# Sheet1.net
KiCad netlist of a schematic drawn in Altium Designer
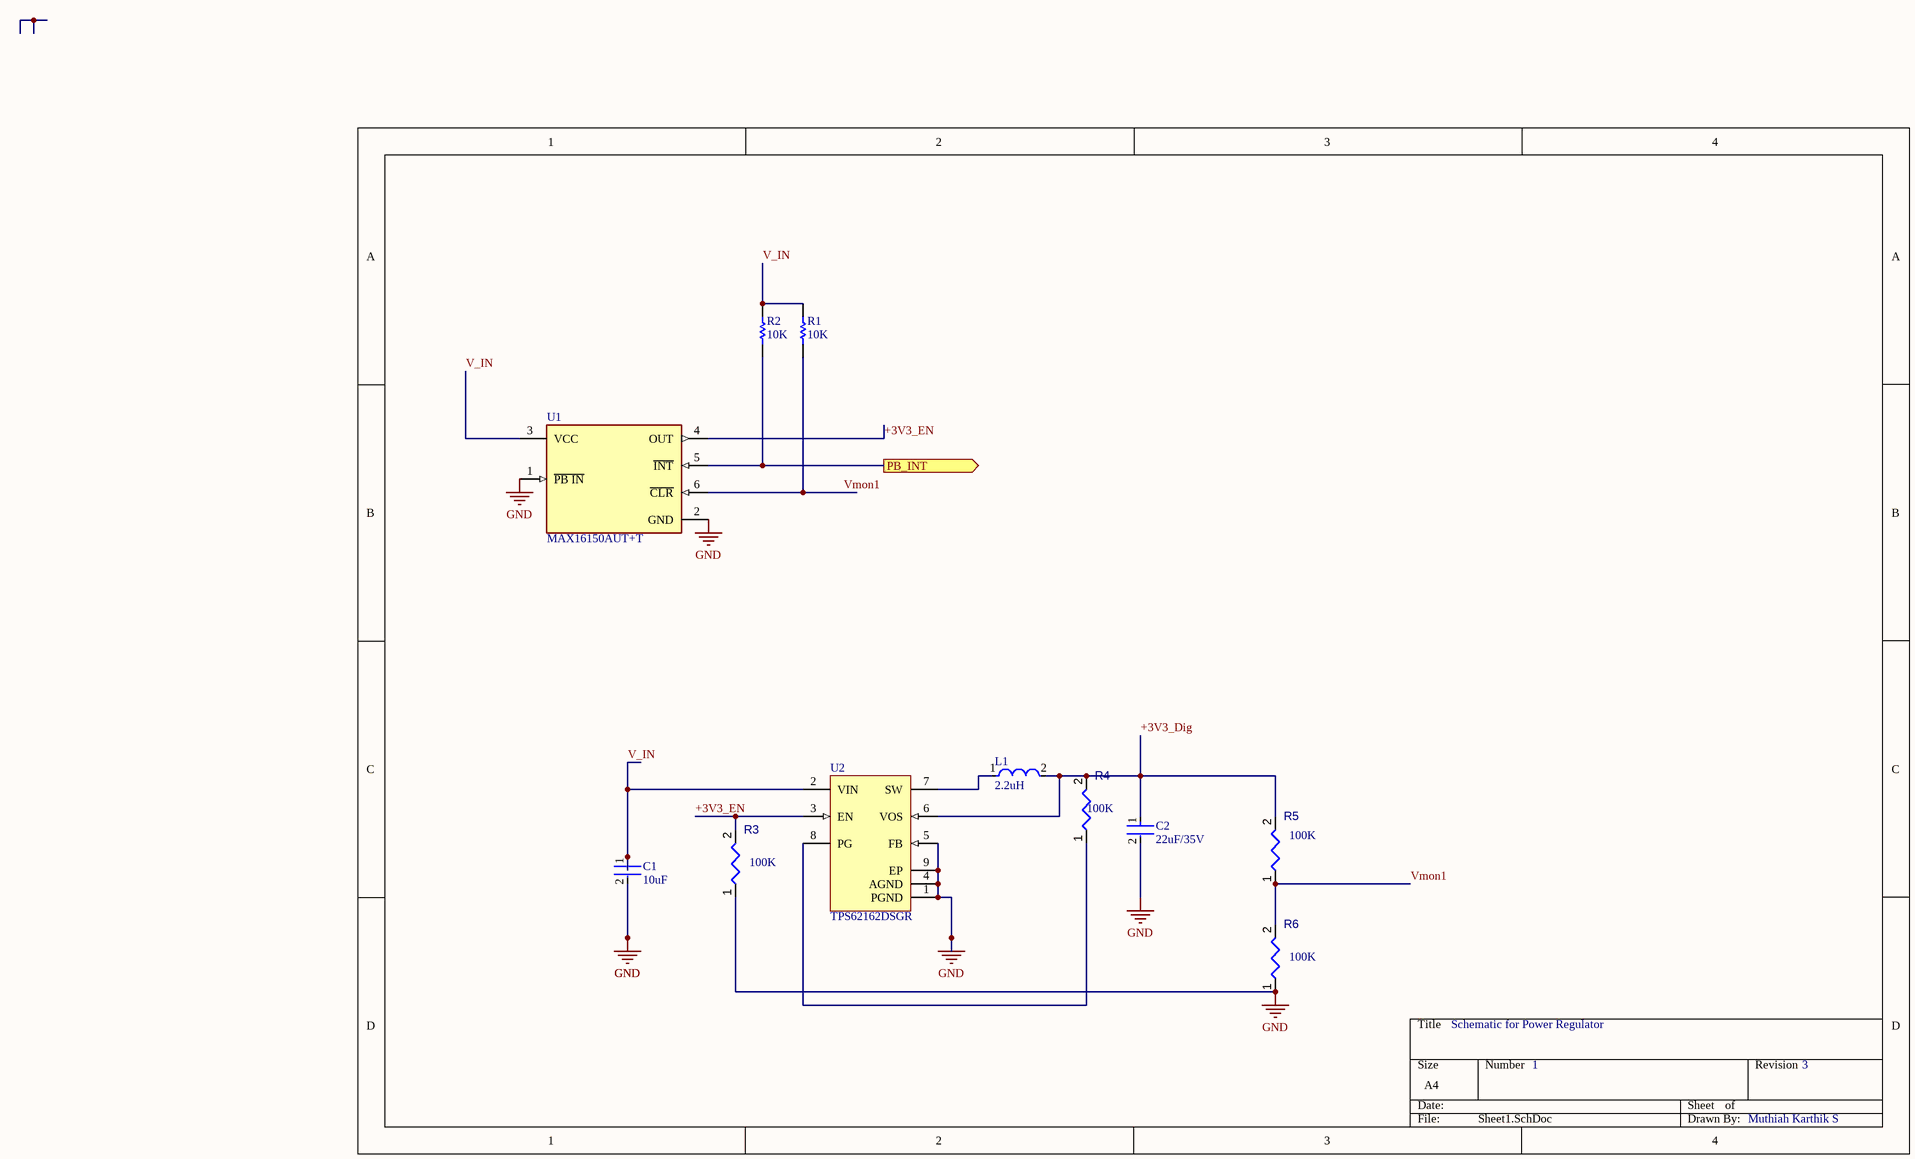
[diagram p0: Sheet1.SchDoc]

(export (version "E")
  (design (tool "Eeschema 10.0.6"))
  (components
    (comp (ref "C1")
      (value "10uF")
      (footprint "FP-CL21-IPC_C")
      (description "CL21 Series 0805 150nF 25V ±10% Tolerance X7R Multilayer Ceramic Chip Capacitor")
      (fields (field (name "TOLERANCE") "10%"))
      (libsource (lib "Altium Content Vault") (part "b4654b650e69147ec39a6b967a45e02"))
    )
    (comp (ref "C2")
      (value "22uF/35V")
      (footprint "FP-CL21-IPC_C")
      (description "CL21 Series 0805 150nF 25V ±10% Tolerance X7R Multilayer Ceramic Chip Capacitor")
      (fields (field (name "TOLERANCE") "10%"))
      (libsource (lib "Altium Content Vault") (part "b4654b650e69147ec39a6b967a45e02"))
    )
    (comp (ref "L1")
      (value "2.2uH")
      (footprint "FP-LQW15AN_00-W0_6-0_1-MFG")
      (description "Wire Wound RF Inductor 2.9nH ±0.5nH 750mA 0.07Ω 0402 (1005)")
      (libsource (lib "Altium Content Vault") (part "725321dda6339637d4d059423bc1c3c"))
    )
    (comp (ref "R1")
      (value "10K")
      (footprint "RESC2013X60X35NL10T20")
      (description "Chip Resistor, 10 KOhm, +/- 1%, 0.125 W, -55 to 155 degC, 0805 (2012 Metric), RoHS, Tape and Reel")
      (fields (field (name "MANUFACTURER") "Yageo"))
      (libsource (lib "Altium Content Vault") (part "RES-2"))
    )
    (comp (ref "R2")
      (value "10K")
      (footprint "RESC2013X60X35NL10T20")
      (description "Chip Resistor, 10 KOhm, +/- 1%, 0.125 W, -55 to 155 degC, 0805 (2012 Metric), RoHS, Tape and Reel")
      (fields (field (name "MANUFACTURER") "Yageo"))
      (libsource (lib "Altium Content Vault") (part "RES-2"))
    )
    (comp (ref "R3")
      (value "100K")
      (footprint "RESC2013X50X35ML15T15")
      (description "Chip Resistor, 10 KOhm, +/- 1%, 125 mW, -55 to 155 degC, 0805 (2012 Metric)")
      (fields (field (name "TOLERANCE") "1%") (field (name "POWER") "125mW"))
      (libsource (lib "MKs Altium Cloud") (part "RES-2"))
    )
    (comp (ref "R4")
      (value "100K")
      (footprint "RESC2013X50X35ML15T15")
      (description "Chip Resistor, 10 KOhm, +/- 1%, 125 mW, -55 to 155 degC, 0805 (2012 Metric)")
      (fields (field (name "TOLERANCE") "1%") (field (name "POWER") "125mW"))
      (libsource (lib "MKs Altium Cloud") (part "RES-2"))
    )
    (comp (ref "R5")
      (value "100K")
      (footprint "RESC2013X50X35ML15T15")
      (description "Chip Resistor, 10 KOhm, +/- 1%, 125 mW, -55 to 155 degC, 0805 (2012 Metric)")
      (fields (field (name "TOLERANCE") "1%") (field (name "POWER") "125mW"))
      (libsource (lib "MKs Altium Cloud") (part "RES-2"))
    )
    (comp (ref "R6")
      (value "100K")
      (footprint "RESC2013X50X35ML15T15")
      (description "Chip Resistor, 10 KOhm, +/- 1%, 125 mW, -55 to 155 degC, 0805 (2012 Metric)")
      (fields (field (name "TOLERANCE") "1%") (field (name "POWER") "125mW"))
      (libsource (lib "MKs Altium Cloud") (part "RES-2"))
    )
    (comp (ref "U1")
      (value "MAX16150AUT+T")
      (footprint "FP-U6-1-MFG")
      (description "IC SUPERVISOR 1 CHANNEL SOT23-6")
      (libsource (lib "Altium Content Vault") (part "36a392858d03d148bb8ce7f45f4b5f9"))
    )
    (comp (ref "U2")
      (value "TPS62162DSGR")
      (footprint "DSG0008A_V")
      (fields (field (name "MANUFACTURER") "Texas Instruments"))
      (libsource (lib "Altium Content Vault") (part "TI-TPS62162DSG8-1600X900TP"))
    )
  )
  (nets
    (net (code "1") (name "/+3V3_Dig") (class "Default")
      (node (ref "C2") (pin "1") (pinfunction "1_1") (pintype "passive"))
      (node (ref "L1") (pin "2") (pinfunction "2_2") (pintype "passive"))
      (node (ref "R4") (pin "2") (pinfunction "2_2") (pintype "passive"))
      (node (ref "R5") (pin "2") (pinfunction "2_2") (pintype "passive"))
      (node (ref "U2") (pin "6") (pinfunction "VOS_6") (pintype "input"))
    )
    (net (code "2") (name "/+3V3_EN") (class "Default")
      (node (ref "R3") (pin "2") (pinfunction "2_2") (pintype "passive"))
      (node (ref "U1") (pin "4") (pinfunction "OUT_4") (pintype "output"))
      (node (ref "U2") (pin "3") (pinfunction "EN_3") (pintype "input"))
    )
    (net (code "4") (name "/PB_INT") (class "Default")
      (node (ref "R2") (pin "1") (pinfunction "1_1") (pintype "passive"))
      (node (ref "U1") (pin "5") (pinfunction "~{INT}_5") (pintype "input"))
    )
    (net (code "5") (name "/V_IN") (class "Default")
      (node (ref "C1") (pin "1") (pinfunction "1_1") (pintype "passive"))
      (node (ref "R1") (pin "2") (pinfunction "2_2") (pintype "passive"))
      (node (ref "R2") (pin "2") (pinfunction "2_2") (pintype "passive"))
      (node (ref "U1") (pin "3") (pinfunction "VCC_3") (pintype "power_in"))
      (node (ref "U2") (pin "2") (pinfunction "VIN_2") (pintype "power_in"))
    )
    (net (code "6") (name "/Vmon1") (class "Default")
      (node (ref "R1") (pin "1") (pinfunction "1_1") (pintype "passive"))
      (node (ref "R5") (pin "1") (pinfunction "1_1") (pintype "passive"))
      (node (ref "R6") (pin "2") (pinfunction "2_2") (pintype "passive"))
      (node (ref "U1") (pin "6") (pinfunction "~{CLR}_6") (pintype "input"))
    )
    (net (code "7") (name "GND") (class "Default")
      (node (ref "C1") (pin "2") (pinfunction "2_2") (pintype "passive"))
      (node (ref "C2") (pin "2") (pinfunction "2_2") (pintype "passive"))
      (node (ref "R3") (pin "1") (pinfunction "1_1") (pintype "passive"))
      (node (ref "R6") (pin "1") (pinfunction "1_1") (pintype "passive"))
      (node (ref "U1") (pin "1") (pinfunction "~{PB_IN}_1") (pintype "input"))
      (node (ref "U1") (pin "2") (pinfunction "GND_2") (pintype "power_in"))
      (node (ref "U2") (pin "1") (pinfunction "PGND_1") (pintype "power_in"))
      (node (ref "U2") (pin "4") (pinfunction "AGND_4") (pintype "power_in"))
      (node (ref "U2") (pin "5") (pinfunction "FB_5") (pintype "input"))
      (node (ref "U2") (pin "9") (pinfunction "EP_9") (pintype "power_in"))
    )
    (net (code "8") (name "Net-(U2-PG)") (class "Default")
      (node (ref "R4") (pin "1") (pinfunction "1_1") (pintype "passive"))
      (node (ref "U2") (pin "8") (pinfunction "PG_8") (pintype "tri_state"))
    )
    (net (code "9") (name "Net-(U2-SW)") (class "Default")
      (node (ref "L1") (pin "1") (pinfunction "1_1") (pintype "passive"))
      (node (ref "U2") (pin "7") (pinfunction "SW_7") (pintype "power_in"))
    )
  )
)
